# FUSB302-Breakout-ODG.net
KiCad netlist of a schematic drawn in EAGLE
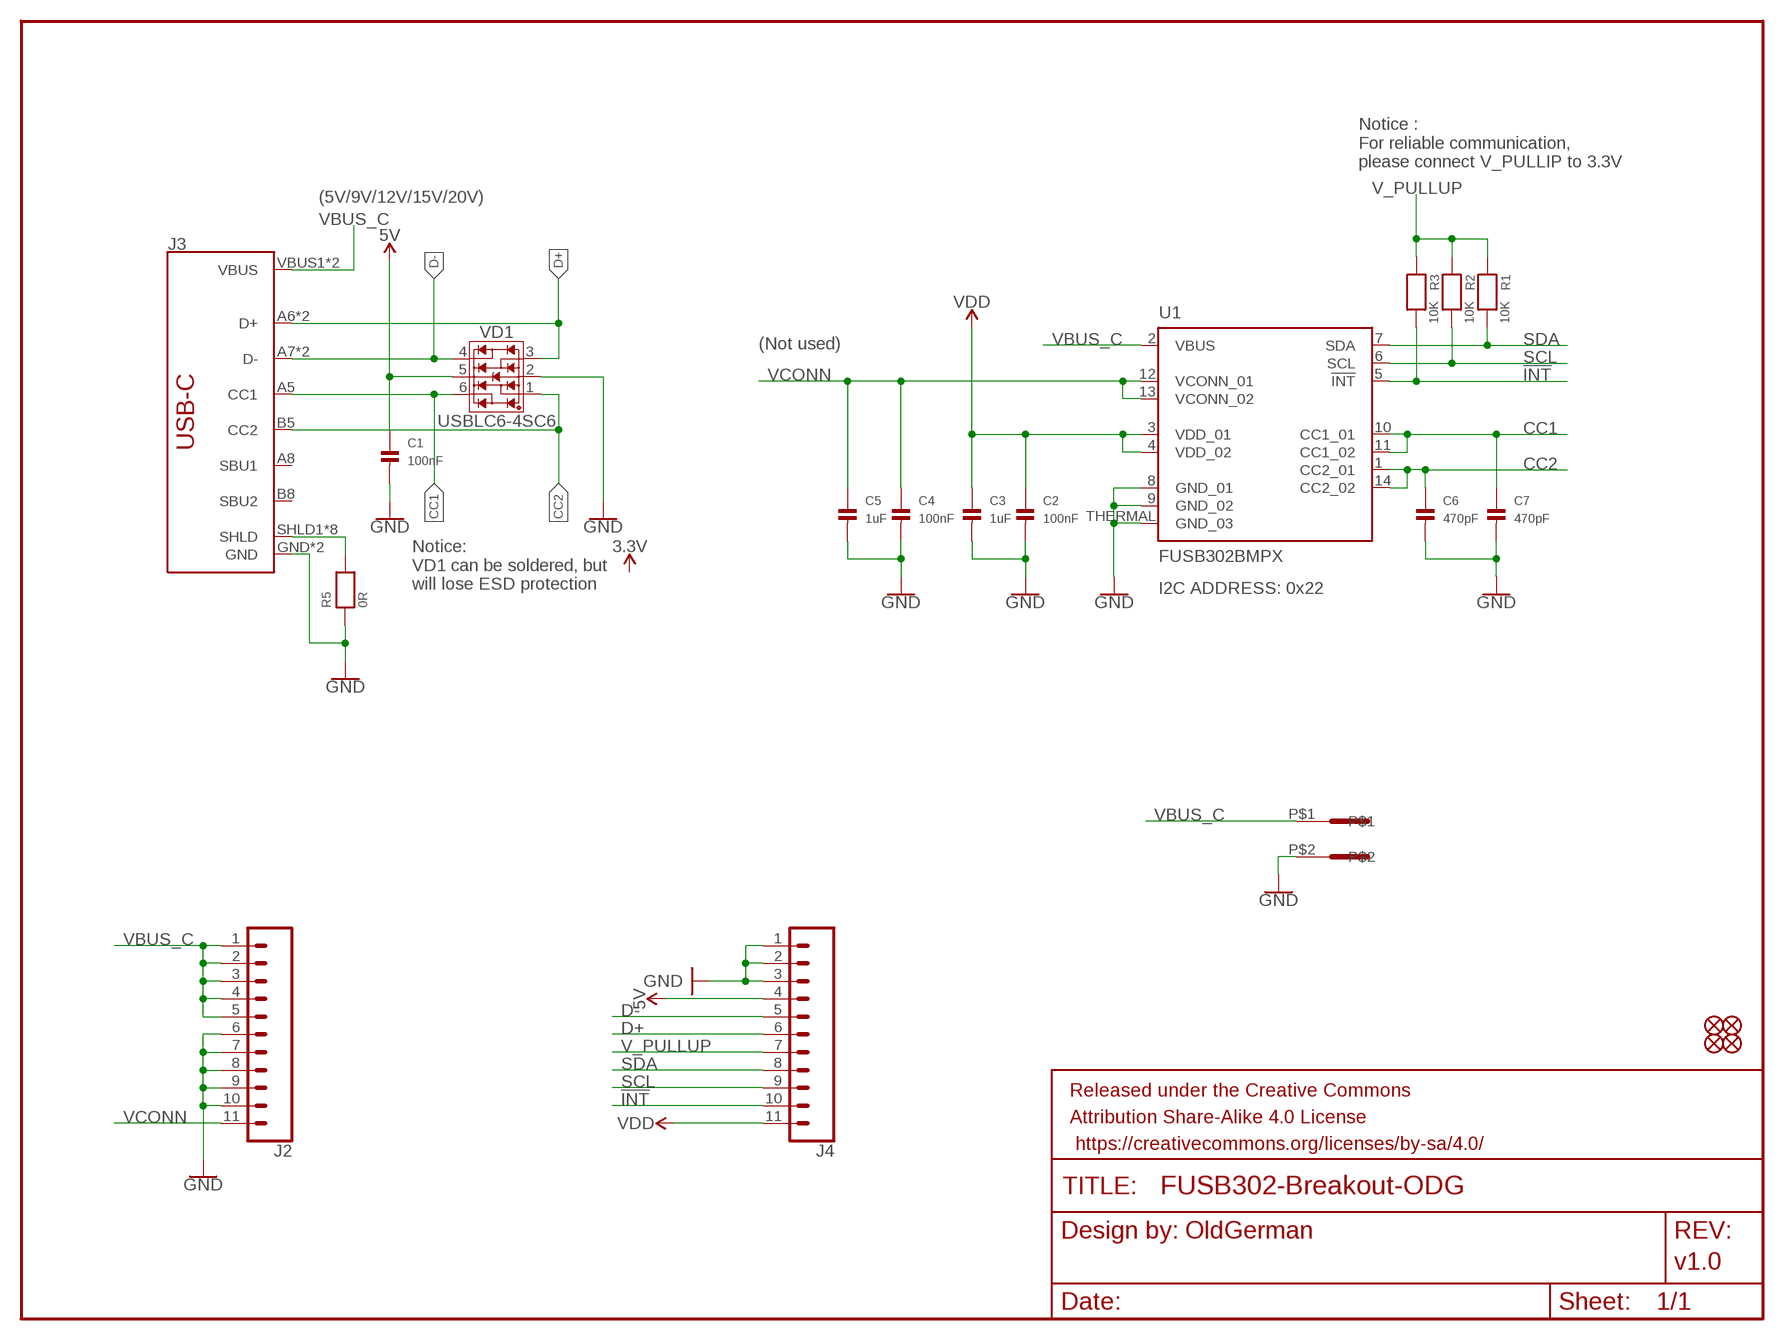
[diagram p0: schematic, sheet 1]

(export (version "E")
  (design (tool "Eeschema 10.0.6"))
  (components
    (comp (ref "C1")
      (value "100nF")
      (footprint "eagle-import:0603")
      (libsource (lib "eagle-import") (part "CAP_CERAMIC0603"))
    )
    (comp (ref "C2")
      (value "100nF")
      (footprint "eagle-import:0603")
      (libsource (lib "eagle-import") (part "CAP_CERAMIC0603"))
    )
    (comp (ref "C3")
      (value "1uF")
      (footprint "eagle-import:0603")
      (libsource (lib "eagle-import") (part "CAP_CERAMIC0603"))
    )
    (comp (ref "C4")
      (value "100nF")
      (footprint "eagle-import:0603")
      (libsource (lib "eagle-import") (part "CAP_CERAMIC0603"))
    )
    (comp (ref "C5")
      (value "1uF")
      (footprint "eagle-import:0603")
      (libsource (lib "eagle-import") (part "CAP_CERAMIC0603"))
    )
    (comp (ref "C6")
      (value "470pF")
      (footprint "eagle-import:0603")
      (libsource (lib "eagle-import") (part "CAP_CERAMIC0603"))
    )
    (comp (ref "C7")
      (value "470pF")
      (footprint "eagle-import:0603")
      (libsource (lib "eagle-import") (part "CAP_CERAMIC0603"))
    )
    (comp (ref "FD5")
      (value "FIDUCIAL_MINI1X2")
      (footprint "eagle-import:FIDUCIAL-1X2")
      (libsource (lib "eagle-import") (part "FIDUCIAL_MINI1X2"))
    )
    (comp (ref "FD6")
      (value "FIDUCIAL_MINI1X2")
      (footprint "eagle-import:FIDUCIAL-1X2")
      (libsource (lib "eagle-import") (part "FIDUCIAL_MINI1X2"))
    )
    (comp (ref "FD7")
      (value "FIDUCIAL_MINI1X2")
      (footprint "eagle-import:FIDUCIAL-1X2")
      (libsource (lib "eagle-import") (part "FIDUCIAL_MINI1X2"))
    )
    (comp (ref "FD8")
      (value "FIDUCIAL_MINI1X2")
      (footprint "eagle-import:FIDUCIAL-1X2")
      (libsource (lib "eagle-import") (part "FIDUCIAL_MINI1X2"))
    )
    (comp (ref "FRAME2")
      (value "FRAME-LETTER")
      (footprint "eagle-import:CREATIVE_COMMONS")
      (libsource (lib "eagle-import") (part "FRAME-LETTER"))
    )
    (comp (ref "J2")
      (value "CONN_11")
      (footprint "eagle-import:1X11")
      (libsource (lib "eagle-import") (part "CONN_11"))
    )
    (comp (ref "J3")
      (value "USB_C_LONG-SYMBOL2-LAYER")
      (footprint "eagle-import:USB-C-16P")
      (libsource (lib "eagle-import") (part "USB_C_LONG-SYMBOL2-LAYER"))
    )
    (comp (ref "J4")
      (value "CONN_11")
      (footprint "eagle-import:1X11")
      (libsource (lib "eagle-import") (part "CONN_11"))
    )
    (comp (ref "R1")
      (value "10K")
      (footprint "eagle-import:0603")
      (libsource (lib "eagle-import") (part "RESISTOR0603"))
    )
    (comp (ref "R2")
      (value "10K")
      (footprint "eagle-import:0603")
      (libsource (lib "eagle-import") (part "RESISTOR0603"))
    )
    (comp (ref "R3")
      (value "10K")
      (footprint "eagle-import:0603")
      (libsource (lib "eagle-import") (part "RESISTOR0603"))
    )
    (comp (ref "R5")
      (value "0R")
      (footprint "eagle-import:0603")
      (libsource (lib "eagle-import") (part "RESISTOR0603"))
    )
    (comp (ref "U$5")
      (value "5.08MM_CONN")
      (footprint "eagle-import:1715250000")
      (libsource (lib "eagle-import") (part "5.08MM_CONN"))
    )
    (comp (ref "U1")
      (value "FUSB302BMPX")
      (footprint "eagle-import:QFN14-2.5X2.5MM")
      (libsource (lib "eagle-import") (part "FUSB302"))
    )
    (comp (ref "VD1")
      (value "USBLC6-4SC6")
      (footprint "eagle-import:SOT23-6")
      (libsource (lib "eagle-import") (part "USBLC6-4SOT23-6"))
    )
  )
  (nets
    (net (code "1") (name "/SCL") (class "Default")
      (node (ref "J4") (pin "9") (pinfunction "9_9") (pintype "passive"))
      (node (ref "R2") (pin "2") (pinfunction "2_2") (pintype "passive"))
      (node (ref "U1") (pin "6") (pinfunction "SCL_6") (pintype "bidirectional"))
    )
    (net (code "2") (name "/SDA") (class "Default")
      (node (ref "J4") (pin "8") (pinfunction "8_8") (pintype "passive"))
      (node (ref "R1") (pin "2") (pinfunction "2_2") (pintype "passive"))
      (node (ref "U1") (pin "7") (pinfunction "SDA_7") (pintype "bidirectional"))
    )
    (net (code "3") (name "/VBUS_C") (class "Default")
      (node (ref "J2") (pin "1") (pinfunction "1_1") (pintype "passive"))
      (node (ref "J2") (pin "2") (pinfunction "2_2") (pintype "passive"))
      (node (ref "J2") (pin "3") (pinfunction "3_3") (pintype "passive"))
      (node (ref "J2") (pin "4") (pinfunction "4_4") (pintype "passive"))
      (node (ref "J2") (pin "5") (pinfunction "5_5") (pintype "passive"))
      (node (ref "J3") (pin "VBUS1") (pinfunction "VBUS_VBUS1") (pintype "bidirectional"))
      (node (ref "J3") (pin "VBUS2") (pinfunction "VBUS_VBUS2") (pintype "bidirectional"))
      (node (ref "U$5") (pin "P$1") (pinfunction "P$1_P$1") (pintype "bidirectional"))
      (node (ref "U1") (pin "2") (pinfunction "VBUS_2") (pintype "bidirectional"))
    )
    (net (code "4") (name "/VCONN") (class "Default")
      (node (ref "C4") (pin "1") (pinfunction "P$1_1") (pintype "passive"))
      (node (ref "C5") (pin "1") (pinfunction "P$1_1") (pintype "passive"))
      (node (ref "J2") (pin "11") (pinfunction "11_11") (pintype "passive"))
      (node (ref "U1") (pin "12") (pinfunction "VCONN_01_12") (pintype "bidirectional"))
      (node (ref "U1") (pin "13") (pinfunction "VCONN_02_13") (pintype "bidirectional"))
    )
    (net (code "5") (name "/V_PULLUP") (class "Default")
      (node (ref "J4") (pin "7") (pinfunction "7_7") (pintype "passive"))
      (node (ref "R1") (pin "1") (pinfunction "1_1") (pintype "passive"))
      (node (ref "R2") (pin "1") (pinfunction "1_1") (pintype "passive"))
      (node (ref "R3") (pin "1") (pinfunction "1_1") (pintype "passive"))
    )
    (net (code "6") (name "/~{INT}") (class "Default")
      (node (ref "J4") (pin "10") (pinfunction "10_10") (pintype "passive"))
      (node (ref "R3") (pin "2") (pinfunction "2_2") (pintype "passive"))
      (node (ref "U1") (pin "5") (pinfunction "~{INT}_5") (pintype "bidirectional"))
    )
    (net (code "8") (name "5V") (class "Default")
      (node (ref "C1") (pin "1") (pinfunction "P$1_1") (pintype "passive"))
      (node (ref "J4") (pin "4") (pinfunction "4_4") (pintype "passive"))
      (node (ref "VD1") (pin "5") (pinfunction "P$5_5") (pintype "bidirectional"))
    )
    (net (code "9") (name "CC1") (class "Default")
      (node (ref "C7") (pin "1") (pinfunction "P$1_1") (pintype "passive"))
      (node (ref "J3") (pin "A5") (pinfunction "CC1_A5") (pintype "bidirectional"))
      (node (ref "U1") (pin "10") (pinfunction "CC1_01_10") (pintype "bidirectional"))
      (node (ref "U1") (pin "11") (pinfunction "CC1_02_11") (pintype "bidirectional"))
      (node (ref "VD1") (pin "6") (pinfunction "P$6_6") (pintype "bidirectional"))
    )
    (net (code "10") (name "CC2") (class "Default")
      (node (ref "C6") (pin "1") (pinfunction "P$1_1") (pintype "passive"))
      (node (ref "J3") (pin "B5") (pinfunction "CC2_B5") (pintype "bidirectional"))
      (node (ref "U1") (pin "1") (pinfunction "CC2_01_1") (pintype "bidirectional"))
      (node (ref "U1") (pin "14") (pinfunction "CC2_02_14") (pintype "bidirectional"))
      (node (ref "VD1") (pin "1") (pinfunction "P$1_1") (pintype "bidirectional"))
    )
    (net (code "11") (name "D+") (class "Default")
      (node (ref "J3") (pin "A6") (pinfunction "D+_A6") (pintype "bidirectional"))
      (node (ref "J3") (pin "B6") (pinfunction "D+_B6") (pintype "bidirectional"))
      (node (ref "J4") (pin "6") (pinfunction "6_6") (pintype "passive"))
      (node (ref "VD1") (pin "3") (pinfunction "P$3_3") (pintype "bidirectional"))
    )
    (net (code "12") (name "D-") (class "Default")
      (node (ref "J3") (pin "A7") (pinfunction "D-_A7") (pintype "bidirectional"))
      (node (ref "J3") (pin "B7") (pinfunction "D-_B7") (pintype "bidirectional"))
      (node (ref "J4") (pin "5") (pinfunction "5_5") (pintype "passive"))
      (node (ref "VD1") (pin "4") (pinfunction "P$4_4") (pintype "bidirectional"))
    )
    (net (code "13") (name "GND") (class "Default")
      (node (ref "C1") (pin "2") (pinfunction "P$2_2") (pintype "passive"))
      (node (ref "C2") (pin "2") (pinfunction "P$2_2") (pintype "passive"))
      (node (ref "C3") (pin "2") (pinfunction "P$2_2") (pintype "passive"))
      (node (ref "C4") (pin "2") (pinfunction "P$2_2") (pintype "passive"))
      (node (ref "C5") (pin "2") (pinfunction "P$2_2") (pintype "passive"))
      (node (ref "C6") (pin "2") (pinfunction "P$2_2") (pintype "passive"))
      (node (ref "C7") (pin "2") (pinfunction "P$2_2") (pintype "passive"))
      (node (ref "J2") (pin "10") (pinfunction "10_10") (pintype "passive"))
      (node (ref "J2") (pin "6") (pinfunction "6_6") (pintype "passive"))
      (node (ref "J2") (pin "7") (pinfunction "7_7") (pintype "passive"))
      (node (ref "J2") (pin "8") (pinfunction "8_8") (pintype "passive"))
      (node (ref "J2") (pin "9") (pinfunction "9_9") (pintype "passive"))
      (node (ref "J3") (pin "GND") (pinfunction "GND_GND") (pintype "bidirectional"))
      (node (ref "J3") (pin "GND2") (pinfunction "GND_GND2") (pintype "bidirectional"))
      (node (ref "J4") (pin "1") (pinfunction "1_1") (pintype "passive"))
      (node (ref "J4") (pin "2") (pinfunction "2_2") (pintype "passive"))
      (node (ref "J4") (pin "3") (pinfunction "3_3") (pintype "passive"))
      (node (ref "R5") (pin "1") (pinfunction "1_1") (pintype "passive"))
      (node (ref "U$5") (pin "P$2") (pinfunction "P$2_P$2") (pintype "bidirectional"))
      (node (ref "U1") (pin "8") (pinfunction "GND_01_8") (pintype "bidirectional"))
      (node (ref "U1") (pin "9") (pinfunction "GND_02_9") (pintype "bidirectional"))
      (node (ref "U1") (pin "THERMAL") (pinfunction "GND_03_THERMAL") (pintype "bidirectional"))
      (node (ref "VD1") (pin "2") (pinfunction "P$2_2") (pintype "bidirectional"))
    )
    (net (code "14") (name "Net-(J3-SHLD-PadSHLD1)") (class "Default")
      (node (ref "J3") (pin "SHLD1") (pinfunction "SHLD_SHLD1") (pintype "bidirectional"))
      (node (ref "J3") (pin "SHLD2") (pinfunction "SHLD_SHLD2") (pintype "bidirectional"))
      (node (ref "J3") (pin "SHLD3") (pinfunction "SHLD_SHLD3") (pintype "bidirectional"))
      (node (ref "J3") (pin "SHLD4") (pinfunction "SHLD_SHLD4") (pintype "bidirectional"))
      (node (ref "J3") (pin "SHLD5") (pinfunction "SHLD_SHLD5") (pintype "bidirectional"))
      (node (ref "J3") (pin "SHLD6") (pinfunction "SHLD_SHLD6") (pintype "bidirectional"))
      (node (ref "J3") (pin "SHLD7") (pinfunction "SHLD_SHLD7") (pintype "bidirectional"))
      (node (ref "J3") (pin "SHLD8") (pinfunction "SHLD_SHLD8") (pintype "bidirectional"))
      (node (ref "R5") (pin "2") (pinfunction "2_2") (pintype "passive"))
    )
    (net (code "15") (name "VDD") (class "Default")
      (node (ref "C2") (pin "1") (pinfunction "P$1_1") (pintype "passive"))
      (node (ref "C3") (pin "1") (pinfunction "P$1_1") (pintype "passive"))
      (node (ref "J4") (pin "11") (pinfunction "11_11") (pintype "passive"))
      (node (ref "U1") (pin "3") (pinfunction "VDD_01_3") (pintype "bidirectional"))
      (node (ref "U1") (pin "4") (pinfunction "VDD_02_4") (pintype "bidirectional"))
    )
    (net (code "16") (name "unconnected-(J3-SBU1-PadA8)") (class "Default")
      (node (ref "J3") (pin "A8") (pinfunction "SBU1_A8") (pintype "bidirectional"))
    )
    (net (code "17") (name "unconnected-(J3-SBU2-PadB8)") (class "Default")
      (node (ref "J3") (pin "B8") (pinfunction "SBU2_B8") (pintype "bidirectional"))
    )
  )
)
